# ESRA_tsk3000_-_Copy.net
KiCad netlist of a schematic drawn in Altium Designer
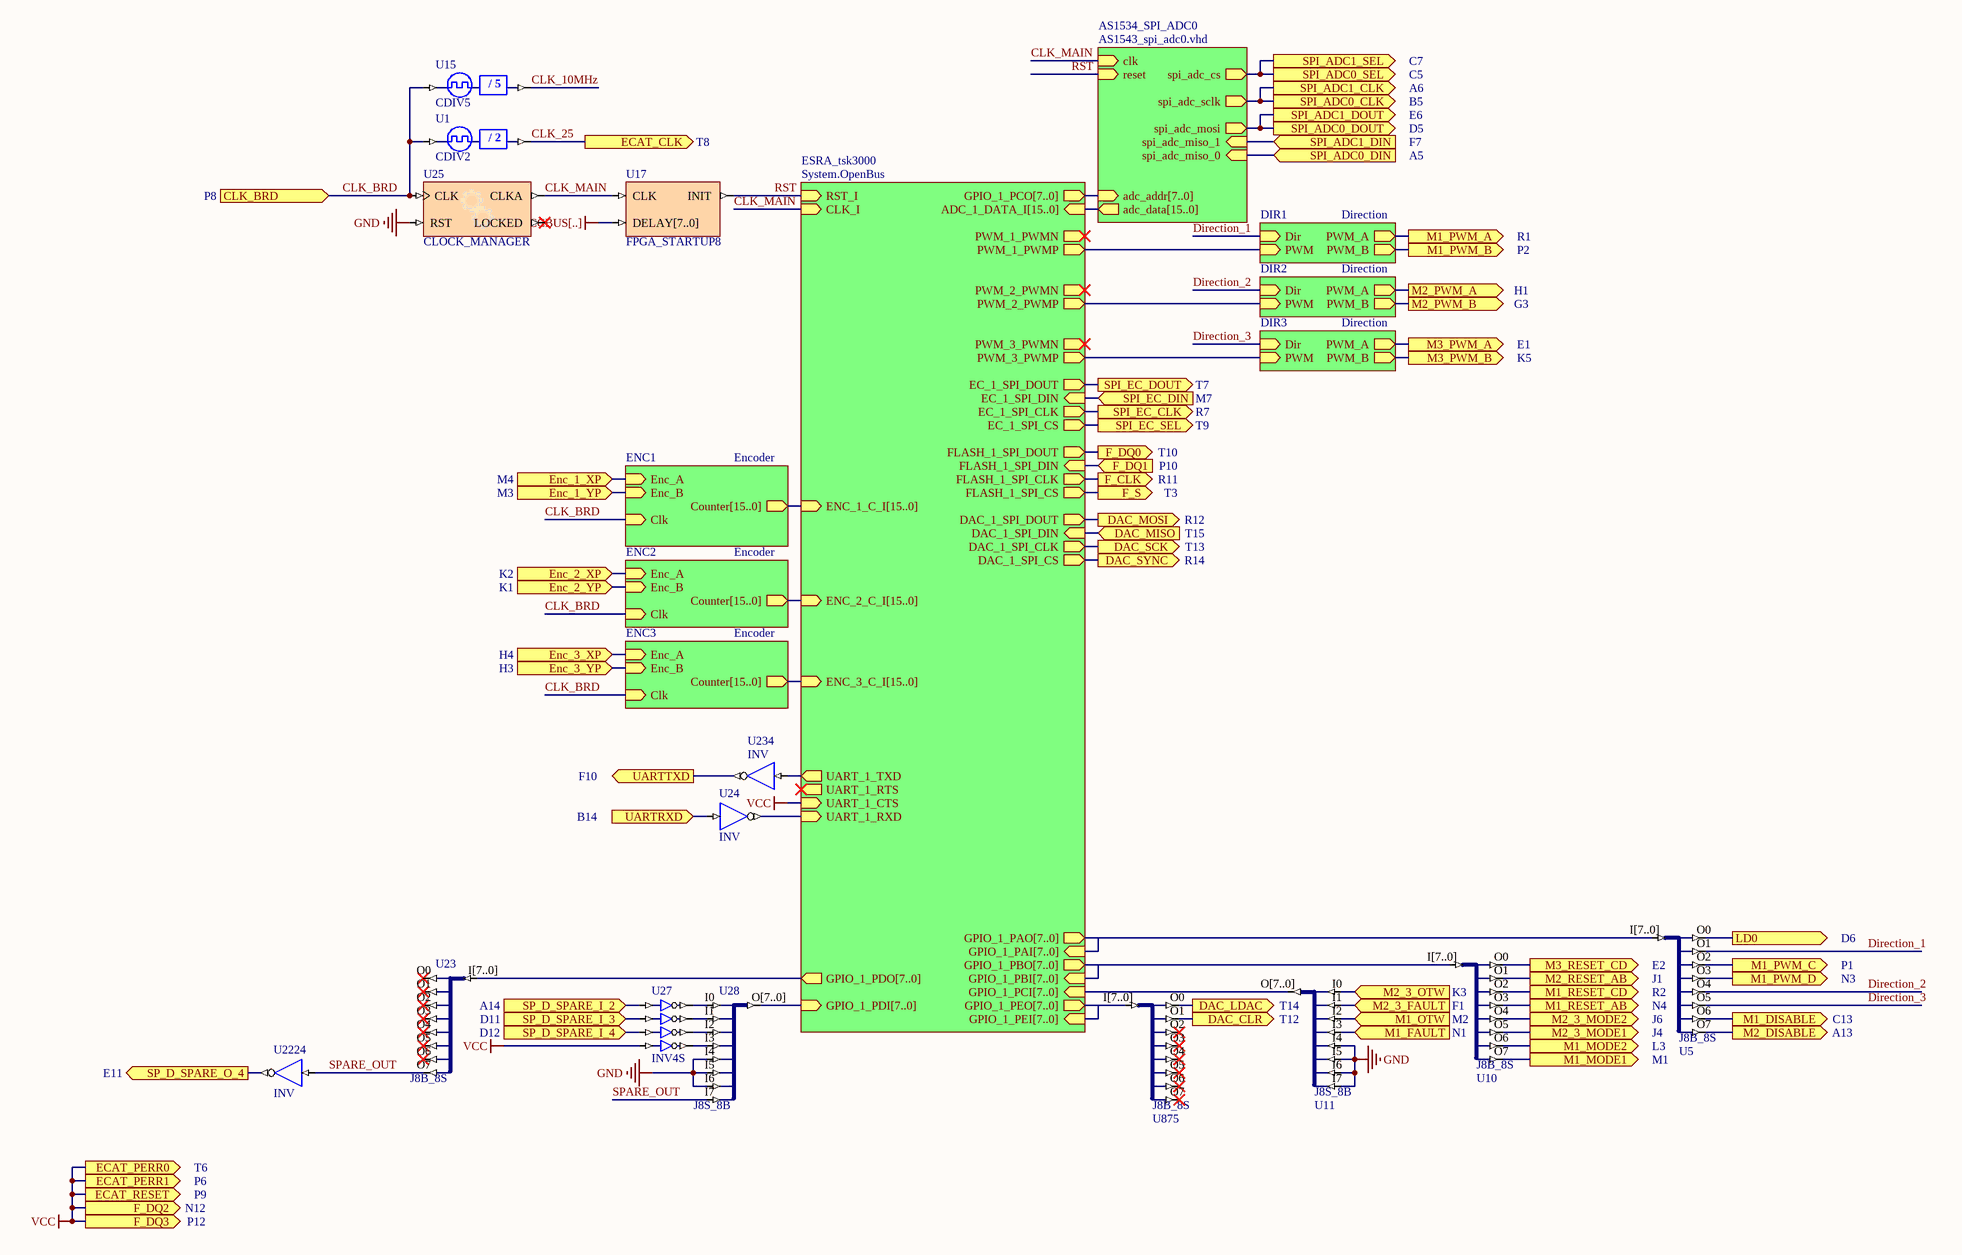
[diagram p0: ESRA_tsk3000 - Copy.SchDoc]

(export (version "E")
  (design (tool "Eeschema 10.0.6"))
  (components
    (comp (ref "U1")
      (value "CDIV2")
      (description "Clock Divider by 2")
      (fields (field (name "PUBLISHER") "Altium Limited"))
      (libsource (lib "FPGA Generic") (part "CDIV2"))
    )
    (comp (ref "U5")
      (value "J8B_8S")
      (description "8-Bit input bus to 8 single pin outputs")
      (fields (field (name "PUBLISHER") "Altium Limited"))
      (libsource (lib "FPGA Generic") (part "J8B_8S"))
    )
    (comp (ref "U10")
      (value "J8B_8S")
      (description "8-Bit input bus to 8 single pin outputs")
      (fields (field (name "PUBLISHER") "Altium Limited"))
      (libsource (lib "FPGA Generic") (part "J8B_8S"))
    )
    (comp (ref "U11")
      (value "J8S_8B")
      (description "8 Single pin inputs to single 8-Bit output bus")
      (fields (field (name "PUBLISHER") "Altium Limited"))
      (libsource (lib "FPGA Generic") (part "J8S_8B"))
    )
    (comp (ref "U15")
      (value "CDIV5")
      (description "Clock Divider by 5")
      (fields (field (name "PUBLISHER") "Altium Limited"))
      (libsource (lib "FPGA Generic") (part "CDIV5"))
    )
    (comp (ref "U17")
      (value "FPGA_STARTUP8")
      (description "FPGA Startup With 8 Bit Delay")
      (fields (field (name "PUBLISHER") "Altium Limited"))
      (libsource (lib "FPGA Generic") (part "FPGA_STARTUP8"))
    )
    (comp (ref "U23")
      (value "J8B_8S")
      (description "8-Bit input bus to 8 single pin outputs")
      (fields (field (name "PUBLISHER") "Altium Limited"))
      (libsource (lib "FPGA Generic") (part "J8B_8S"))
    )
    (comp (ref "U24")
      (value "INV")
      (description "Inverter")
      (fields (field (name "PUBLISHER") "Altium Limited"))
      (libsource (lib "FPGA Generic") (part "INV"))
    )
    (comp (ref "U25")
      (value "CLOCK_MANAGER")
      (description "Configurable Clock Manager")
      (fields (field (name "PUBLISHER") "Altium Limited"))
      (libsource (lib "FPGA Configurable Generic") (part "CLOCKMANAGER"))
    )
    (comp (ref "U27")
      (value "INV4S")
      (description "4-Bit Inverter, Single Pin Version")
      (fields (field (name "PUBLISHER") "Altium Limited"))
      (libsource (lib "FPGA Generic") (part "INV4S"))
    )
    (comp (ref "U28")
      (value "J8S_8B")
      (description "8 Single pin inputs to single 8-Bit output bus")
      (fields (field (name "PUBLISHER") "Altium Limited"))
      (libsource (lib "FPGA Generic") (part "J8S_8B"))
    )
    (comp (ref "U234")
      (value "INV")
      (description "Inverter")
      (fields (field (name "PUBLISHER") "Altium Limited"))
      (libsource (lib "FPGA Generic") (part "INV"))
    )
    (comp (ref "U875")
      (value "J8B_8S")
      (description "8-Bit input bus to 8 single pin outputs")
      (fields (field (name "PUBLISHER") "Altium Limited"))
      (libsource (lib "FPGA Generic") (part "J8B_8S"))
    )
    (comp (ref "U2224")
      (value "INV")
      (description "Inverter")
      (fields (field (name "PUBLISHER") "Altium Limited"))
      (libsource (lib "FPGA Generic") (part "INV"))
    )
  )
  (nets
    (net (code "1") (name "/CLK_10MHz") (class "Default")
      (node (ref "U15") (pin "CLKDV") (pinfunction "CLKDV_CLKDV") (pintype "output"))
    )
    (net (code "2") (name "/CLK_25") (class "Default")
      (node (ref "U1") (pin "CLKDV") (pinfunction "CLKDV_CLKDV") (pintype "output"))
    )
    (net (code "3") (name "/CLK_BRD") (class "Default")
      (node (ref "U1") (pin "CLKIN") (pinfunction "CLKIN_CLKIN") (pintype "input"))
      (node (ref "U15") (pin "CLKIN") (pinfunction "CLKIN_CLKIN") (pintype "input"))
      (node (ref "U25") (pin "CLK") (pinfunction "CLK_CLK") (pintype "input"))
    )
    (net (code "4") (name "/CLK_MAIN") (class "Default")
      (node (ref "U17") (pin "CLK") (pinfunction "CLK_CLK") (pintype "input"))
      (node (ref "U25") (pin "CLKA") (pinfunction "CLKA_CLKA") (pintype "output"))
    )
    (net (code "8") (name "/DAC_CLR") (class "Default")
      (node (ref "U875") (pin "O1") (pinfunction "O1_O1") (pintype "output"))
    )
    (net (code "9") (name "/DAC_LDAC") (class "Default")
      (node (ref "U875") (pin "O0") (pinfunction "O0_O0") (pintype "output"))
    )
    (net (code "14") (name "/Direction_1") (class "Default")
      (node (ref "U5") (pin "O1") (pinfunction "O1_O1") (pintype "output"))
    )
    (net (code "15") (name "/Direction_2") (class "Default")
      (node (ref "U5") (pin "O4") (pinfunction "O4_O4") (pintype "output"))
    )
    (net (code "16") (name "/Direction_3") (class "Default")
      (node (ref "U5") (pin "O5") (pinfunction "O5_O5") (pintype "output"))
    )
    (net (code "28") (name "/GPIO_1_PAO[7..0]") (class "Default")
      (node (ref "U5") (pin "I[7..0]") (pinfunction "I[7..0]_I[7..0]") (pintype "input"))
    )
    (net (code "30") (name "/GPIO_1_PBO[7..0]") (class "Default")
      (node (ref "U10") (pin "I[7..0]") (pinfunction "I[7..0]_I[7..0]") (pintype "input"))
    )
    (net (code "31") (name "/GPIO_1_PCI[7..0]") (class "Default")
      (node (ref "U11") (pin "O[7..0]") (pinfunction "O[7..0]_O[7..0]") (pintype "output"))
    )
    (net (code "33") (name "/GPIO_1_PDI[7..0]") (class "Default")
      (node (ref "U28") (pin "O[7..0]") (pinfunction "O[7..0]_O[7..0]") (pintype "output"))
    )
    (net (code "34") (name "/GPIO_1_PDO[7..0]") (class "Default")
      (node (ref "U23") (pin "I[7..0]") (pinfunction "I[7..0]_I[7..0]") (pintype "input"))
    )
    (net (code "36") (name "/GPIO_1_PEO[7..0]") (class "Default")
      (node (ref "U875") (pin "I[7..0]") (pinfunction "I[7..0]_I[7..0]") (pintype "input"))
    )
    (net (code "37") (name "/LD0") (class "Default")
      (node (ref "U5") (pin "O0") (pinfunction "O0_O0") (pintype "output"))
    )
    (net (code "38") (name "/M1_DISABLE") (class "Default")
      (node (ref "U5") (pin "O6") (pinfunction "O6_O6") (pintype "output"))
    )
    (net (code "39") (name "/M1_FAULT") (class "Default")
      (node (ref "U11") (pin "I3") (pinfunction "I3_I3") (pintype "input"))
    )
    (net (code "40") (name "/M1_MODE1") (class "Default")
      (node (ref "U10") (pin "O7") (pinfunction "O7_O7") (pintype "output"))
    )
    (net (code "41") (name "/M1_MODE2") (class "Default")
      (node (ref "U10") (pin "O6") (pinfunction "O6_O6") (pintype "output"))
    )
    (net (code "42") (name "/M1_OTW") (class "Default")
      (node (ref "U11") (pin "I2") (pinfunction "I2_I2") (pintype "input"))
    )
    (net (code "45") (name "/M1_PWM_C") (class "Default")
      (node (ref "U5") (pin "O2") (pinfunction "O2_O2") (pintype "output"))
    )
    (net (code "46") (name "/M1_PWM_D") (class "Default")
      (node (ref "U5") (pin "O3") (pinfunction "O3_O3") (pintype "output"))
    )
    (net (code "47") (name "/M1_RESET_AB") (class "Default")
      (node (ref "U10") (pin "O3") (pinfunction "O3_O3") (pintype "output"))
    )
    (net (code "48") (name "/M1_RESET_CD") (class "Default")
      (node (ref "U10") (pin "O2") (pinfunction "O2_O2") (pintype "output"))
    )
    (net (code "49") (name "/M2_3_FAULT") (class "Default")
      (node (ref "U11") (pin "I1") (pinfunction "I1_I1") (pintype "input"))
    )
    (net (code "50") (name "/M2_3_MODE1") (class "Default")
      (node (ref "U10") (pin "O5") (pinfunction "O5_O5") (pintype "output"))
    )
    (net (code "51") (name "/M2_3_MODE2") (class "Default")
      (node (ref "U10") (pin "O4") (pinfunction "O4_O4") (pintype "output"))
    )
    (net (code "52") (name "/M2_3_OTW") (class "Default")
      (node (ref "U11") (pin "I0") (pinfunction "I0_I0") (pintype "input"))
    )
    (net (code "53") (name "/M2_DISABLE") (class "Default")
      (node (ref "U5") (pin "O7") (pinfunction "O7_O7") (pintype "output"))
    )
    (net (code "56") (name "/M2_RESET_AB") (class "Default")
      (node (ref "U10") (pin "O1") (pinfunction "O1_O1") (pintype "output"))
    )
    (net (code "59") (name "/M3_RESET_CD") (class "Default")
      (node (ref "U10") (pin "O0") (pinfunction "O0_O0") (pintype "output"))
    )
    (net (code "66") (name "/RST") (class "Default")
      (node (ref "U17") (pin "INIT") (pinfunction "INIT_INIT") (pintype "output"))
    )
    (net (code "67") (name "/SPARE_OUT") (class "Default")
      (node (ref "U2224") (pin "I") (pinfunction "I_I") (pintype "input"))
      (node (ref "U23") (pin "O7") (pinfunction "O7_O7") (pintype "output"))
      (node (ref "U28") (pin "I7") (pinfunction "I7_I7") (pintype "input"))
    )
    (net (code "77") (name "/SP_D_SPARE_I_2") (class "Default")
      (node (ref "U27") (pin "I0") (pinfunction "I0_I0") (pintype "input"))
    )
    (net (code "78") (name "/SP_D_SPARE_I_3") (class "Default")
      (node (ref "U27") (pin "I1") (pinfunction "I1_I1") (pintype "input"))
    )
    (net (code "79") (name "/SP_D_SPARE_I_4") (class "Default")
      (node (ref "U27") (pin "I2") (pinfunction "I2_I2") (pintype "input"))
    )
    (net (code "80") (name "/SP_D_SPARE_O_4") (class "Default")
      (node (ref "U2224") (pin "O") (pinfunction "O_O") (pintype "output"))
    )
    (net (code "81") (name "/UARTRXD") (class "Default")
      (node (ref "U24") (pin "I") (pinfunction "I_I") (pintype "input"))
    )
    (net (code "82") (name "/UARTTXD") (class "Default")
      (node (ref "U234") (pin "O") (pinfunction "O_O") (pintype "output"))
    )
    (net (code "84") (name "/UART_1_RXD") (class "Default")
      (node (ref "U24") (pin "O") (pinfunction "O_O") (pintype "output"))
    )
    (net (code "85") (name "/UART_1_TXD") (class "Default")
      (node (ref "U234") (pin "I") (pinfunction "I_I") (pintype "input"))
    )
    (net (code "87") (name "GND") (class "Default")
      (node (ref "U11") (pin "I4") (pinfunction "I4_I4") (pintype "input"))
      (node (ref "U11") (pin "I5") (pinfunction "I5_I5") (pintype "input"))
      (node (ref "U11") (pin "I6") (pinfunction "I6_I6") (pintype "input"))
      (node (ref "U11") (pin "I7") (pinfunction "I7_I7") (pintype "input"))
      (node (ref "U25") (pin "RST") (pinfunction "RST_RST") (pintype "input"))
      (node (ref "U28") (pin "I4") (pinfunction "I4_I4") (pintype "input"))
      (node (ref "U28") (pin "I5") (pinfunction "I5_I5") (pintype "input"))
      (node (ref "U28") (pin "I6") (pinfunction "I6_I6") (pintype "input"))
    )
    (net (code "88") (name "Net-(U27-PadO0)") (class "Default")
      (node (ref "U27") (pin "O0") (pinfunction "O0_O0") (pintype "output"))
      (node (ref "U28") (pin "I0") (pinfunction "I0_I0") (pintype "input"))
    )
    (net (code "89") (name "Net-(U27-PadO1)") (class "Default")
      (node (ref "U27") (pin "O1") (pinfunction "O1_O1") (pintype "output"))
      (node (ref "U28") (pin "I1") (pinfunction "I1_I1") (pintype "input"))
    )
    (net (code "90") (name "Net-(U27-PadO2)") (class "Default")
      (node (ref "U27") (pin "O2") (pinfunction "O2_O2") (pintype "output"))
      (node (ref "U28") (pin "I2") (pinfunction "I2_I2") (pintype "input"))
    )
    (net (code "91") (name "Net-(U27-PadO3)") (class "Default")
      (node (ref "U27") (pin "O3") (pinfunction "O3_O3") (pintype "output"))
      (node (ref "U28") (pin "I3") (pinfunction "I3_I3") (pintype "input"))
    )
    (net (code "92") (name "VCC") (class "Default")
      (node (ref "U27") (pin "I3") (pinfunction "I3_I3") (pintype "input"))
    )
    (net (code "93") (name "VCCBUS[..]") (class "Default")
      (node (ref "U17") (pin "DELAY[7..0]") (pinfunction "DELAY[7..0]_DELAY[7..0]") (pintype "input"))
    )
    (net (code "94") (name "unconnected-(U23-PadO0)") (class "Default")
      (node (ref "U23") (pin "O0") (pinfunction "O0_O0") (pintype "output+no_connect"))
    )
    (net (code "95") (name "unconnected-(U23-PadO1)") (class "Default")
      (node (ref "U23") (pin "O1") (pinfunction "O1_O1") (pintype "output+no_connect"))
    )
    (net (code "96") (name "unconnected-(U23-PadO2)") (class "Default")
      (node (ref "U23") (pin "O2") (pinfunction "O2_O2") (pintype "output+no_connect"))
    )
    (net (code "97") (name "unconnected-(U23-PadO3)") (class "Default")
      (node (ref "U23") (pin "O3") (pinfunction "O3_O3") (pintype "output+no_connect"))
    )
    (net (code "98") (name "unconnected-(U23-PadO4)") (class "Default")
      (node (ref "U23") (pin "O4") (pinfunction "O4_O4") (pintype "output+no_connect"))
    )
    (net (code "99") (name "unconnected-(U23-PadO5)") (class "Default")
      (node (ref "U23") (pin "O5") (pinfunction "O5_O5") (pintype "output+no_connect"))
    )
    (net (code "100") (name "unconnected-(U23-PadO6)") (class "Default")
      (node (ref "U23") (pin "O6") (pinfunction "O6_O6") (pintype "output+no_connect"))
    )
    (net (code "101") (name "unconnected-(U25-PadLOCKED)") (class "Default")
      (node (ref "U25") (pin "LOCKED") (pinfunction "LOCKED_LOCKED") (pintype "output+no_connect"))
    )
    (net (code "102") (name "unconnected-(U875-PadO2)") (class "Default")
      (node (ref "U875") (pin "O2") (pinfunction "O2_O2") (pintype "output+no_connect"))
    )
    (net (code "103") (name "unconnected-(U875-PadO3)") (class "Default")
      (node (ref "U875") (pin "O3") (pinfunction "O3_O3") (pintype "output+no_connect"))
    )
    (net (code "104") (name "unconnected-(U875-PadO4)") (class "Default")
      (node (ref "U875") (pin "O4") (pinfunction "O4_O4") (pintype "output+no_connect"))
    )
    (net (code "105") (name "unconnected-(U875-PadO5)") (class "Default")
      (node (ref "U875") (pin "O5") (pinfunction "O5_O5") (pintype "output+no_connect"))
    )
    (net (code "106") (name "unconnected-(U875-PadO6)") (class "Default")
      (node (ref "U875") (pin "O6") (pinfunction "O6_O6") (pintype "output+no_connect"))
    )
    (net (code "107") (name "unconnected-(U875-PadO7)") (class "Default")
      (node (ref "U875") (pin "O7") (pinfunction "O7_O7") (pintype "output+no_connect"))
    )
  )
)
